# W040X.net
KiCad netlist of a schematic drawn in EAGLE
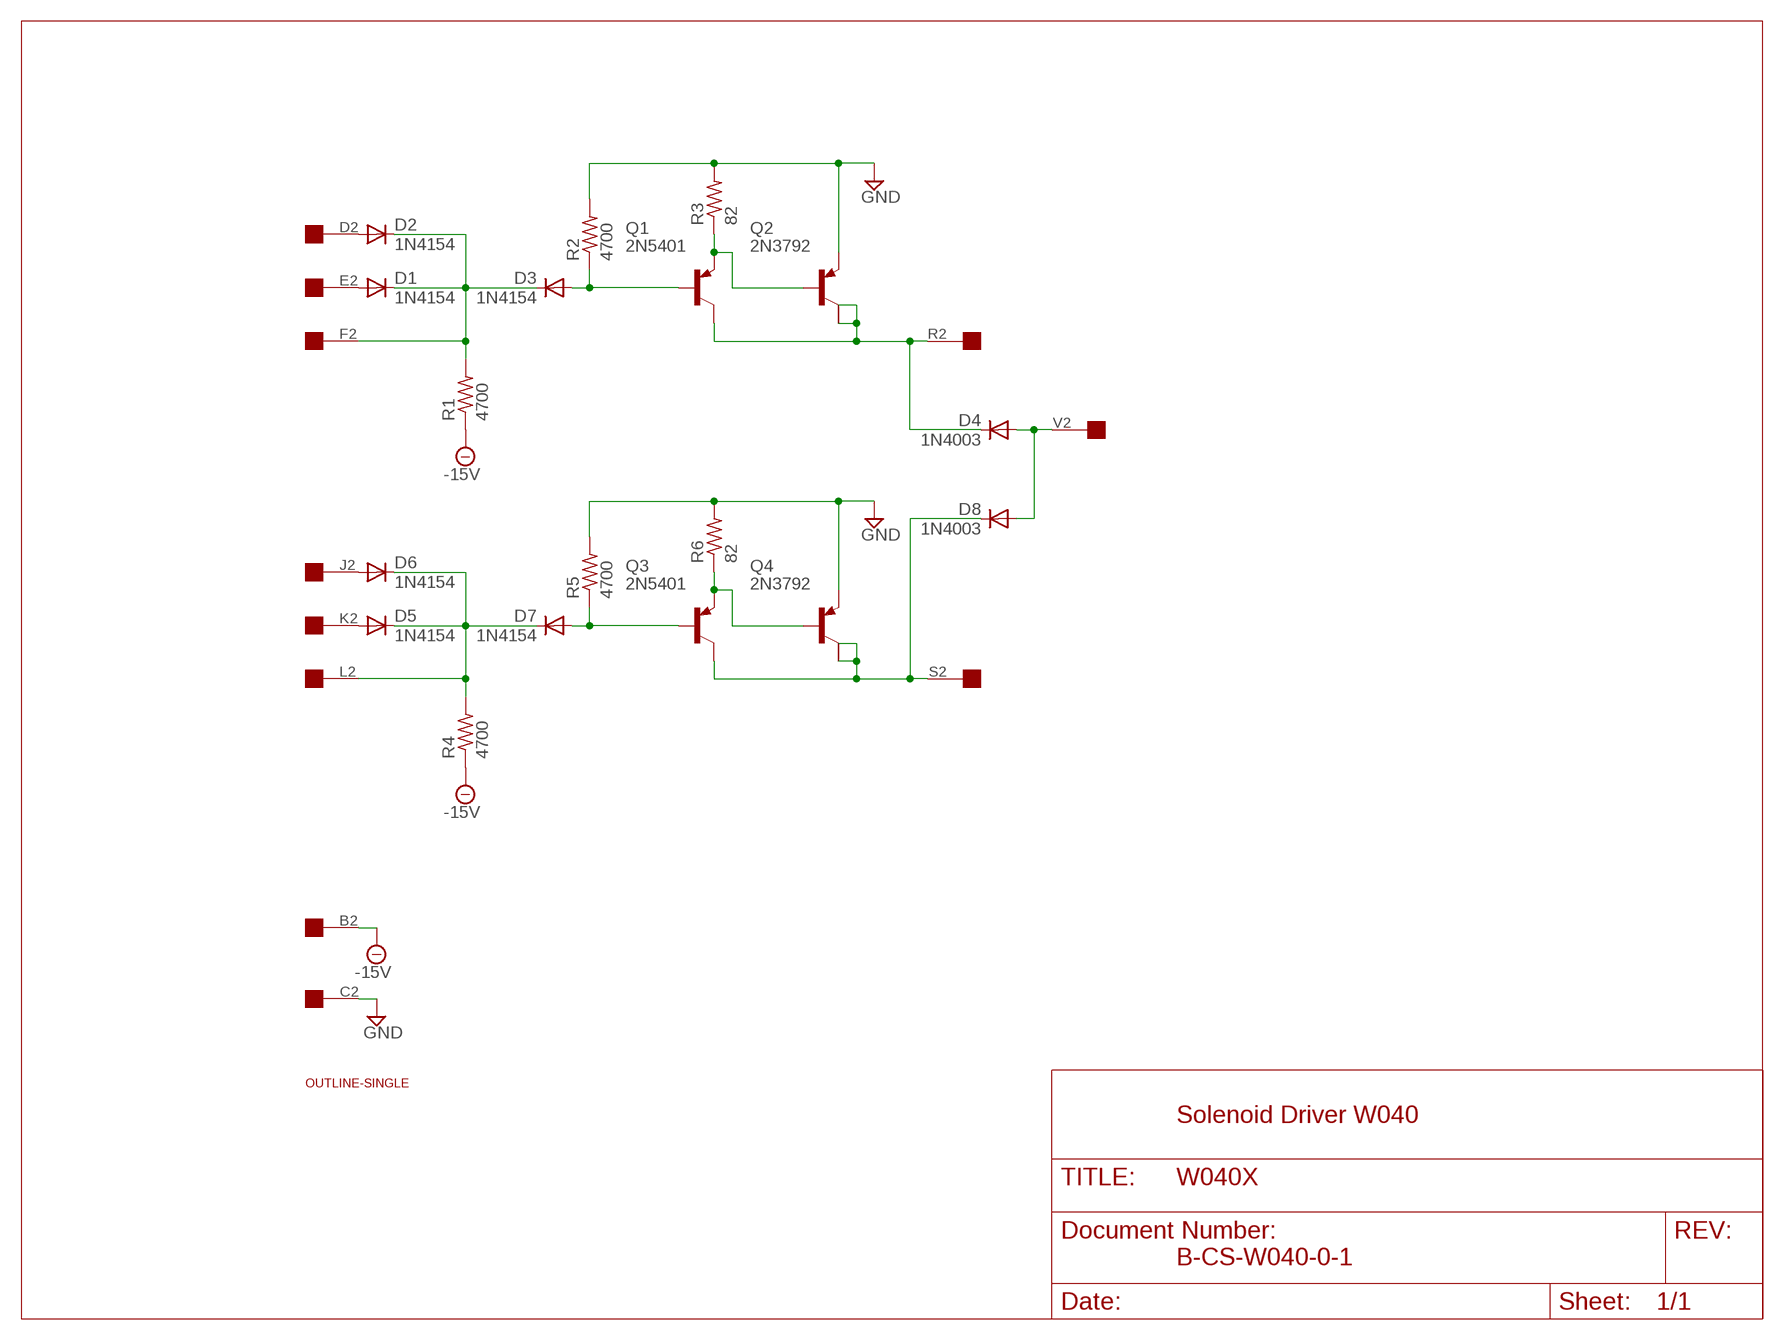
[diagram p0: schematic, sheet 1]

(export (version "E")
  (design (tool "Eeschema 10.0.6"))
  (components
    (comp (ref "D1")
      (value "1N4154")
      (footprint "eagle-import:DO35-10")
      (libsource (lib "eagle-import") (part "1N4148"))
    )
    (comp (ref "D2")
      (value "1N4154")
      (footprint "eagle-import:DO35-10")
      (libsource (lib "eagle-import") (part "1N4148"))
    )
    (comp (ref "D3")
      (value "1N4154")
      (footprint "eagle-import:DO35-10")
      (libsource (lib "eagle-import") (part "1N4148"))
    )
    (comp (ref "D4")
      (value "1N4003")
      (footprint "eagle-import:DO41-10")
      (libsource (lib "eagle-import") (part "1N4004"))
    )
    (comp (ref "D5")
      (value "1N4154")
      (footprint "eagle-import:DO35-10")
      (libsource (lib "eagle-import") (part "1N4148"))
    )
    (comp (ref "D6")
      (value "1N4154")
      (footprint "eagle-import:DO35-10")
      (libsource (lib "eagle-import") (part "1N4148"))
    )
    (comp (ref "D7")
      (value "1N4154")
      (footprint "eagle-import:DO35-10")
      (libsource (lib "eagle-import") (part "1N4148"))
    )
    (comp (ref "D8")
      (value "1N4003")
      (footprint "eagle-import:DO41-10")
      (libsource (lib "eagle-import") (part "1N4004"))
    )
    (comp (ref "Q1")
      (value "2N5401")
      (footprint "eagle-import:TO39")
      (libsource (lib "eagle-import") (part "2N2904"))
    )
    (comp (ref "Q2")
      (value "2N3792")
      (footprint "eagle-import:TO3")
      (libsource (lib "eagle-import") (part "2N4902"))
    )
    (comp (ref "Q3")
      (value "2N5401")
      (footprint "eagle-import:TO39")
      (libsource (lib "eagle-import") (part "2N2904"))
    )
    (comp (ref "Q4")
      (value "2N3792")
      (footprint "eagle-import:TO3")
      (libsource (lib "eagle-import") (part "2N4902"))
    )
    (comp (ref "R1")
      (value "4700")
      (footprint "eagle-import:0207_10")
      (libsource (lib "eagle-import") (part "R-US_0207/10"))
    )
    (comp (ref "R2")
      (value "4700")
      (footprint "eagle-import:0207_10")
      (libsource (lib "eagle-import") (part "R-US_0207/10"))
    )
    (comp (ref "R3")
      (value "82")
      (footprint "eagle-import:0207_10")
      (libsource (lib "eagle-import") (part "R-US_0207/10"))
    )
    (comp (ref "R4")
      (value "4700")
      (footprint "eagle-import:0207_10")
      (libsource (lib "eagle-import") (part "R-US_0207/10"))
    )
    (comp (ref "R5")
      (value "4700")
      (footprint "eagle-import:0207_10")
      (libsource (lib "eagle-import") (part "R-US_0207/10"))
    )
    (comp (ref "R6")
      (value "82")
      (footprint "eagle-import:0207_10")
      (libsource (lib "eagle-import") (part "R-US_0207/10"))
    )
    (comp (ref "U$1")
      (value "OUTLINE-SINGLE")
      (footprint "eagle-import:SINGLE")
      (libsource (lib "eagle-import") (part "OUTLINE-SINGLE"))
    )
    (comp (ref "U$2")
      (value "EDGE-1")
      (footprint "eagle-import:EDGE-CON1")
      (libsource (lib "eagle-import") (part "EDGE-1"))
    )
  )
  (nets
    (net (code "1") (name "-15V") (class "Default")
      (node (ref "R1") (pin "1") (pinfunction "1_1") (pintype "passive"))
      (node (ref "R4") (pin "1") (pinfunction "1_1") (pintype "passive"))
      (node (ref "U$2") (pin "B2") (pinfunction "1_B2") (pintype "bidirectional"))
    )
    (net (code "2") (name "GND") (class "Default")
      (node (ref "Q2") (pin "E") (pinfunction "E_E") (pintype "passive"))
      (node (ref "Q4") (pin "E") (pinfunction "E_E") (pintype "passive"))
      (node (ref "R2") (pin "2") (pinfunction "2_2") (pintype "passive"))
      (node (ref "R3") (pin "2") (pinfunction "2_2") (pintype "passive"))
      (node (ref "R5") (pin "2") (pinfunction "2_2") (pintype "passive"))
      (node (ref "R6") (pin "2") (pinfunction "2_2") (pintype "passive"))
      (node (ref "U$2") (pin "C2") (pinfunction "1_C2") (pintype "bidirectional"))
    )
    (net (code "3") (name "Net-(Q1-B)") (class "Default")
      (node (ref "D3") (pin "A") (pinfunction "A_A") (pintype "passive"))
      (node (ref "Q1") (pin "2") (pinfunction "B_2") (pintype "passive"))
      (node (ref "R2") (pin "1") (pinfunction "1_1") (pintype "passive"))
    )
    (net (code "4") (name "Net-(Q1-C)") (class "Default")
      (node (ref "D4") (pin "C") (pinfunction "C_C") (pintype "passive"))
      (node (ref "Q1") (pin "3") (pinfunction "C_3") (pintype "passive"))
      (node (ref "Q2") (pin "C") (pinfunction "C_C") (pintype "passive"))
      (node (ref "Q2") (pin "C/") (pinfunction "C/_C/") (pintype "passive"))
      (node (ref "U$2") (pin "R2") (pinfunction "1_R2") (pintype "bidirectional"))
    )
    (net (code "5") (name "Net-(Q1-E)") (class "Default")
      (node (ref "Q1") (pin "1") (pinfunction "E_1") (pintype "passive"))
      (node (ref "Q2") (pin "B") (pinfunction "B_B") (pintype "passive"))
      (node (ref "R3") (pin "1") (pinfunction "1_1") (pintype "passive"))
    )
    (net (code "6") (name "Net-(Q3-B)") (class "Default")
      (node (ref "D7") (pin "A") (pinfunction "A_A") (pintype "passive"))
      (node (ref "Q3") (pin "2") (pinfunction "B_2") (pintype "passive"))
      (node (ref "R5") (pin "1") (pinfunction "1_1") (pintype "passive"))
    )
    (net (code "7") (name "Net-(Q3-C)") (class "Default")
      (node (ref "D8") (pin "C") (pinfunction "C_C") (pintype "passive"))
      (node (ref "Q3") (pin "3") (pinfunction "C_3") (pintype "passive"))
      (node (ref "Q4") (pin "C") (pinfunction "C_C") (pintype "passive"))
      (node (ref "Q4") (pin "C/") (pinfunction "C/_C/") (pintype "passive"))
      (node (ref "U$2") (pin "S2") (pinfunction "1_S2") (pintype "bidirectional"))
    )
    (net (code "8") (name "Net-(Q3-E)") (class "Default")
      (node (ref "Q3") (pin "1") (pinfunction "E_1") (pintype "passive"))
      (node (ref "Q4") (pin "B") (pinfunction "B_B") (pintype "passive"))
      (node (ref "R6") (pin "1") (pinfunction "1_1") (pintype "passive"))
    )
    (net (code "9") (name "Net-(U$2D-1)") (class "Default")
      (node (ref "D2") (pin "A") (pinfunction "A_A") (pintype "passive"))
      (node (ref "U$2") (pin "D2") (pinfunction "1_D2") (pintype "bidirectional"))
    )
    (net (code "10") (name "Net-(U$2E-1)") (class "Default")
      (node (ref "D1") (pin "A") (pinfunction "A_A") (pintype "passive"))
      (node (ref "U$2") (pin "E2") (pinfunction "1_E2") (pintype "bidirectional"))
    )
    (net (code "11") (name "Net-(U$2F-1)") (class "Default")
      (node (ref "D1") (pin "C") (pinfunction "C_C") (pintype "passive"))
      (node (ref "D2") (pin "C") (pinfunction "C_C") (pintype "passive"))
      (node (ref "D3") (pin "C") (pinfunction "C_C") (pintype "passive"))
      (node (ref "R1") (pin "2") (pinfunction "2_2") (pintype "passive"))
      (node (ref "U$2") (pin "F2") (pinfunction "1_F2") (pintype "bidirectional"))
    )
    (net (code "12") (name "Net-(U$2H-1)") (class "Default")
      (node (ref "D6") (pin "A") (pinfunction "A_A") (pintype "passive"))
      (node (ref "U$2") (pin "J2") (pinfunction "1_J2") (pintype "bidirectional"))
    )
    (net (code "13") (name "Net-(U$2I-1)") (class "Default")
      (node (ref "D5") (pin "A") (pinfunction "A_A") (pintype "passive"))
      (node (ref "U$2") (pin "K2") (pinfunction "1_K2") (pintype "bidirectional"))
    )
    (net (code "14") (name "Net-(U$2J-1)") (class "Default")
      (node (ref "D5") (pin "C") (pinfunction "C_C") (pintype "passive"))
      (node (ref "D6") (pin "C") (pinfunction "C_C") (pintype "passive"))
      (node (ref "D7") (pin "C") (pinfunction "C_C") (pintype "passive"))
      (node (ref "R4") (pin "2") (pinfunction "2_2") (pintype "passive"))
      (node (ref "U$2") (pin "L2") (pinfunction "1_L2") (pintype "bidirectional"))
    )
    (net (code "15") (name "Net-(U$2R-1)") (class "Default")
      (node (ref "D4") (pin "A") (pinfunction "A_A") (pintype "passive"))
      (node (ref "D8") (pin "A") (pinfunction "A_A") (pintype "passive"))
      (node (ref "U$2") (pin "V2") (pinfunction "1_V2") (pintype "bidirectional"))
    )
  )
)
